# BMS_V3.net
KiCad netlist of a schematic drawn in Altium Designer
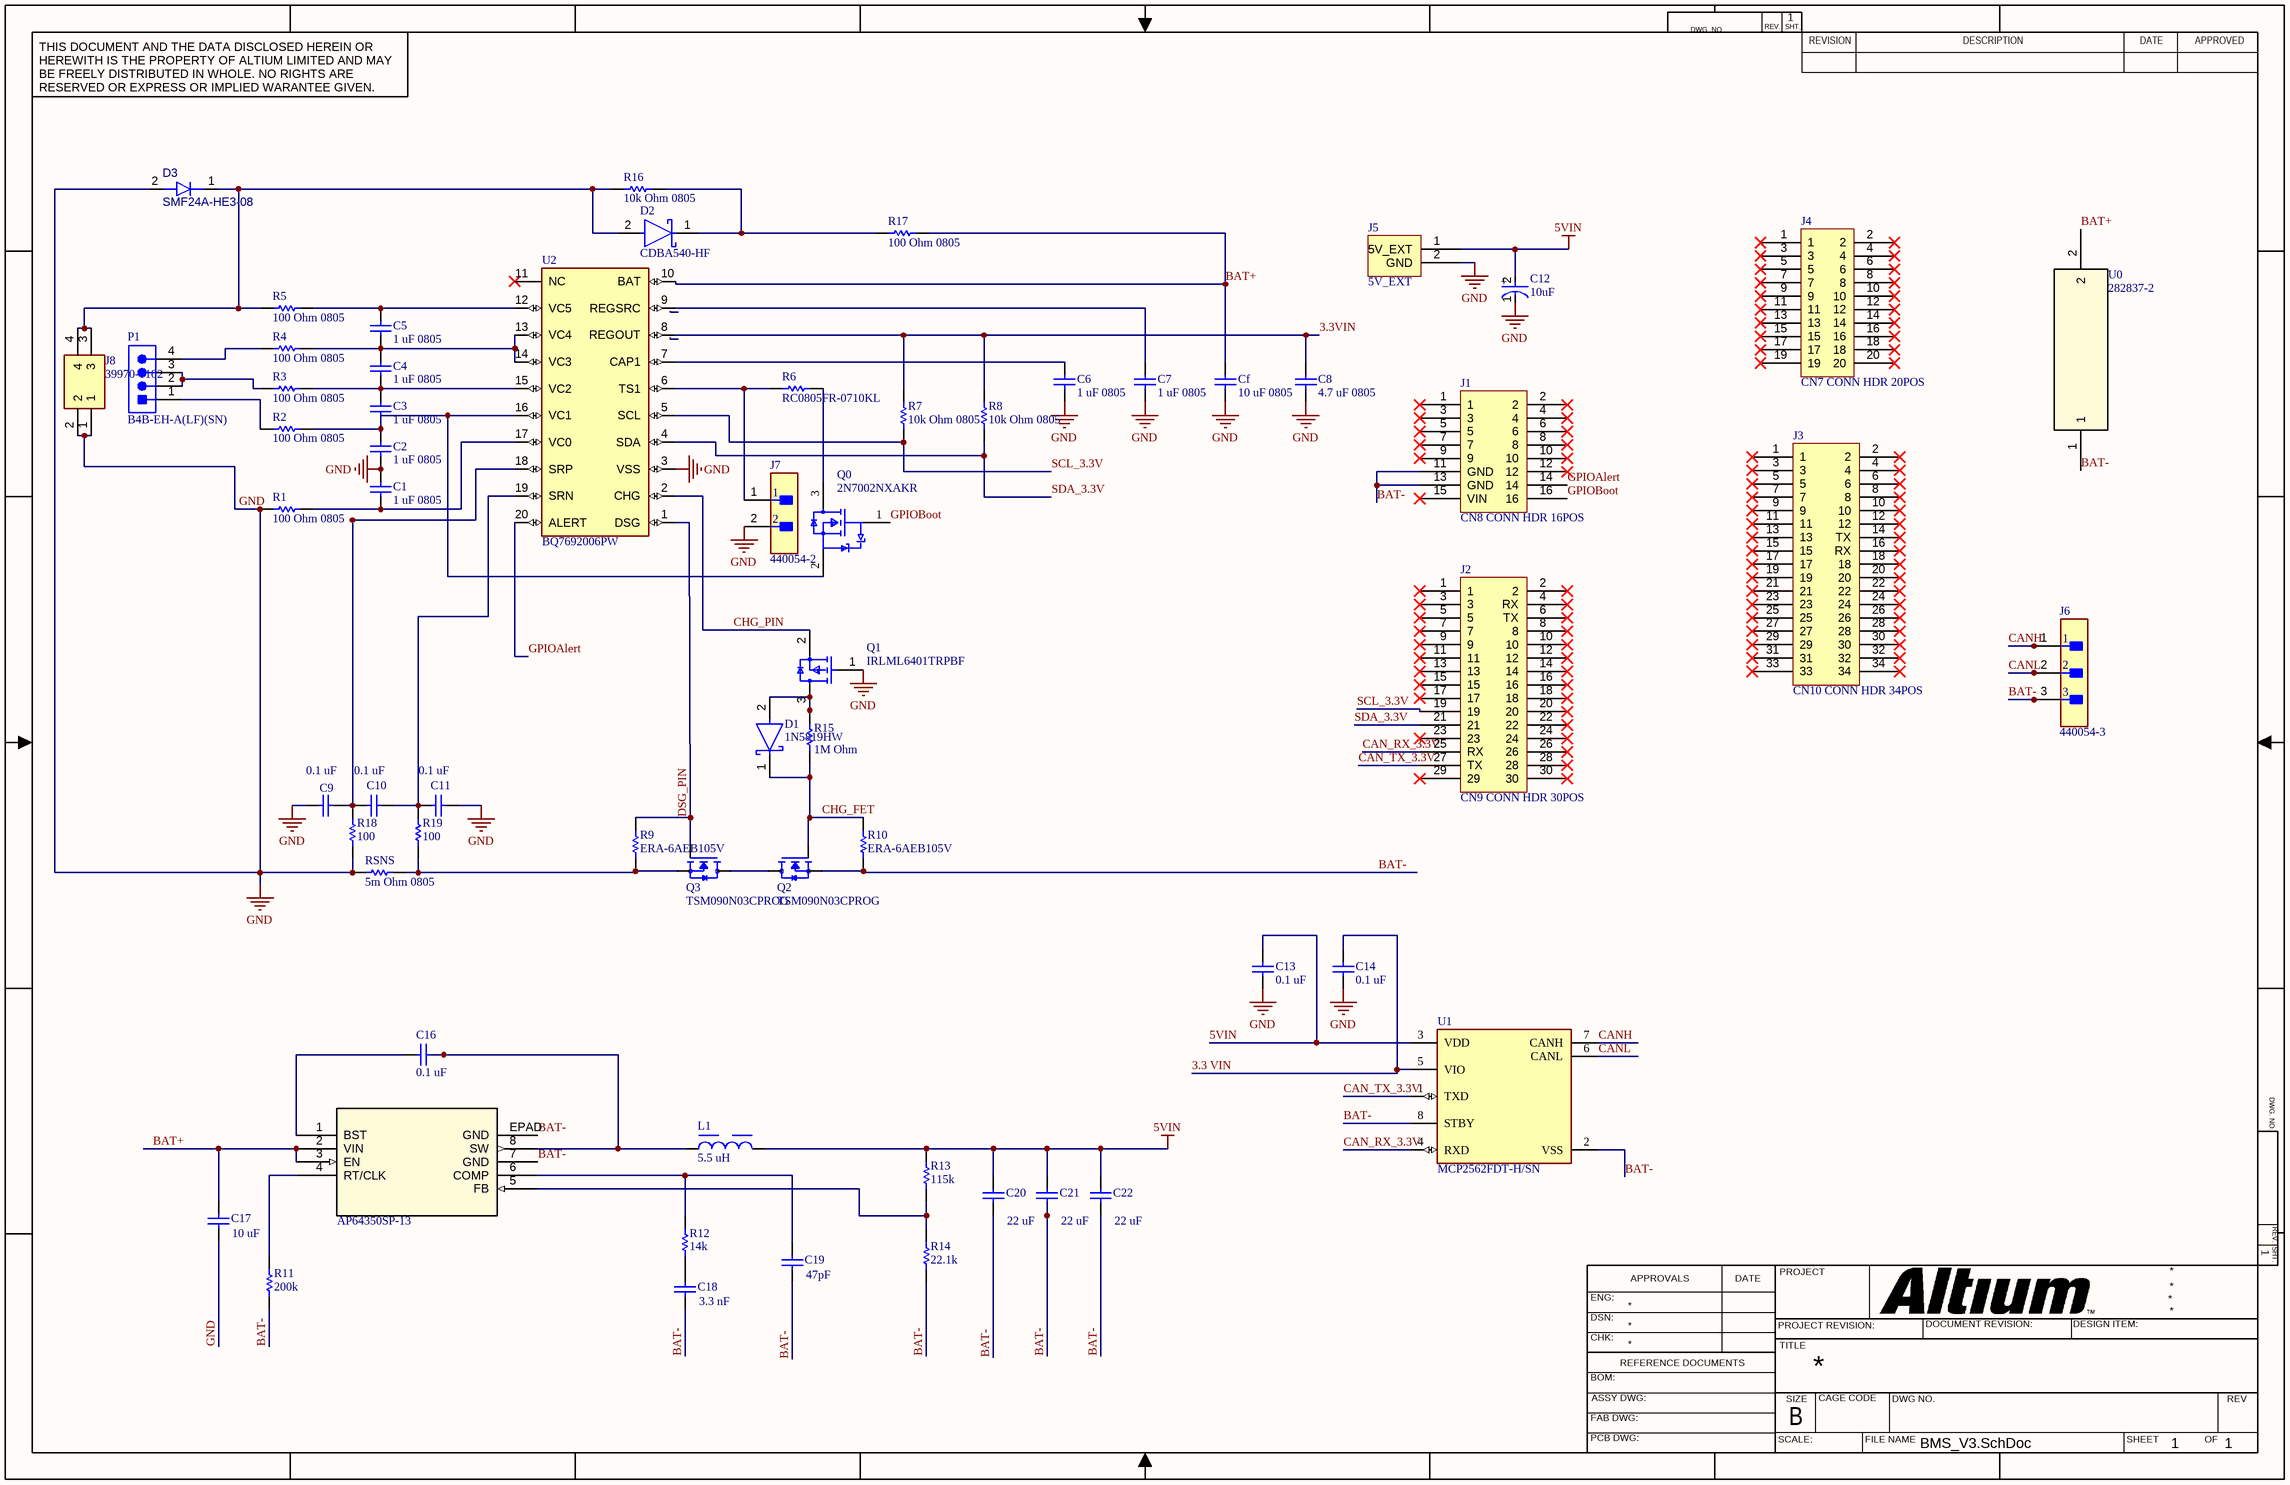
[diagram p0: BMS_V3.SchDoc]

(export (version "E")
  (design (tool "Eeschema 10.0.6"))
  (components
    (comp (ref "C1")
      (value "1 uF 0805")
      (footprint "CAPC2013X140X50LL20T25")
      (fields (field (name "PART NUMBER") "C0805C105K3RACTU") (field (name "MANUFACTURER") "Kemet"))
      (libsource (lib "Altium Content Vault") (part "CAP"))
    )
    (comp (ref "C2")
      (value "1 uF 0805")
      (footprint "CAPC2013X140X50LL20T25")
      (fields (field (name "PART NUMBER") "C0805C105K3RACTU") (field (name "MANUFACTURER") "Kemet"))
      (libsource (lib "Altium Content Vault") (part "CAP"))
    )
    (comp (ref "C3")
      (value "1 uF 0805")
      (footprint "CAPC2013X140X50LL20T25")
      (fields (field (name "PART NUMBER") "C0805C105K3RACTU") (field (name "MANUFACTURER") "Kemet"))
      (libsource (lib "Altium Content Vault") (part "CAP"))
    )
    (comp (ref "C4")
      (value "1 uF 0805")
      (footprint "CAPC2013X140X50LL20T25")
      (fields (field (name "PART NUMBER") "C0805C105K3RACTU") (field (name "MANUFACTURER") "Kemet"))
      (libsource (lib "Altium Content Vault") (part "CAP"))
    )
    (comp (ref "C5")
      (value "1 uF 0805")
      (footprint "CAPC2013X140X50LL20T25")
      (fields (field (name "PART NUMBER") "C0805C105K3RACTU") (field (name "MANUFACTURER") "Kemet"))
      (libsource (lib "Altium Content Vault") (part "CAP"))
    )
    (comp (ref "C6")
      (value "1 uF 0805")
      (footprint "CAPC2013X140X50LL20T25")
      (fields (field (name "PART NUMBER") "C0805C105K3RACTU") (field (name "MANUFACTURER") "Kemet"))
      (libsource (lib "Altium Content Vault") (part "CAP"))
    )
    (comp (ref "C7")
      (value "1 uF 0805")
      (footprint "CAPC2013X140X50LL20T25")
      (fields (field (name "PART NUMBER") "C0805C105K3RACTU") (field (name "MANUFACTURER") "Kemet"))
      (libsource (lib "Altium Content Vault") (part "CAP"))
    )
    (comp (ref "C8")
      (value "4.7 uF 0805")
      (footprint "CAPC2013X140X50LL20T25")
      (fields (field (name "PART NUMBER") "C0805C105K3RACTU") (field (name "MANUFACTURER") "Kemet"))
      (libsource (lib "Altium Content Vault") (part "CAP"))
    )
    (comp (ref "C9")
      (value "0.1 uF")
      (footprint "CAPC2013X140X50LL20T25")
      (fields (field (name "PART NUMBER") "C0805C105K3RACTU") (field (name "MANUFACTURER") "Kemet"))
      (libsource (lib "Altium Content Vault") (part "CAP"))
    )
    (comp (ref "C10")
      (value "0.1 uF")
      (footprint "CAPC2013X140X50LL20T25")
      (fields (field (name "PART NUMBER") "C0805C105K3RACTU") (field (name "MANUFACTURER") "Kemet"))
      (libsource (lib "Altium Content Vault") (part "CAP"))
    )
    (comp (ref "C11")
      (value "0.1 uF")
      (footprint "CAPC2013X140X50LL20T25")
      (fields (field (name "PART NUMBER") "C0805C105K3RACTU") (field (name "MANUFACTURER") "Kemet"))
      (libsource (lib "Altium Content Vault") (part "CAP"))
    )
    (comp (ref "C12")
      (value "10uF")
      (footprint "FP-FKC-MFG")
      (description "CAP ALUM 10UF 20% 50V SMD")
      (fields (field (name "TOLERANCE") "20%") (field (name "VOLTAGE") "50V"))
      (libsource (lib "Altium Content Vault") (part "a00bbbee19879c290e62620ae7e47b1"))
    )
    (comp (ref "C13")
      (value "0.1 uF")
      (footprint "CAPC2013X135X45NL10T25")
      (description "Chip Capacitor, 4.7 uF, +/- 10%, 16 V, -55 to 85 degC, 0805 (2012 Metric), RoHS, Tape and Reel")
      (fields (field (name "TOLERANCE") "10%") (field (name "PARTNUMBER") "GRM21BR61C475KA88L"))
      (libsource (lib "Altium Content Vault") (part "CAP-NP-2"))
    )
    (comp (ref "C14")
      (value "0.1 uF")
      (footprint "CAPC2013X135X45NL10T25")
      (description "Chip Capacitor, 4.7 uF, +/- 10%, 16 V, -55 to 85 degC, 0805 (2012 Metric), RoHS, Tape and Reel")
      (fields (field (name "TOLERANCE") "10%") (field (name "PARTNUMBER") "GRM21BR61C475KA88L"))
      (libsource (lib "Altium Content Vault") (part "CAP-NP-2"))
    )
    (comp (ref "C16")
      (value "0.1 uF")
      (footprint "CAPC2013X135X45NL10T25")
      (description "Chip Capacitor, 4.7 uF, +/- 10%, 16 V, -55 to 85 degC, 0805 (2012 Metric), RoHS, Tape and Reel")
      (fields (field (name "TOLERANCE") "10%") (field (name "PARTNUMBER") "GRM21BR61C475KA88L"))
      (libsource (lib "Altium Content Vault") (part "CAP-NP-2"))
    )
    (comp (ref "C17")
      (value "10 uF")
      (footprint "CAPC2013X135X45NL10T25")
      (description "Chip Capacitor, 4.7 uF, +/- 10%, 16 V, -55 to 85 degC, 0805 (2012 Metric), RoHS, Tape and Reel")
      (fields (field (name "TOLERANCE") "10%") (field (name "PARTNUMBER") "GRM21BR61C475KA88L"))
      (libsource (lib "Altium Content Vault") (part "CAP-NP-2"))
    )
    (comp (ref "C18")
      (value "3.3 nF")
      (footprint "CAPC2013X135X45NL10T25")
      (description "Chip Capacitor, 4.7 uF, +/- 10%, 16 V, -55 to 85 degC, 0805 (2012 Metric), RoHS, Tape and Reel")
      (fields (field (name "TOLERANCE") "10%") (field (name "PARTNUMBER") "GRM21BR61C475KA88L"))
      (libsource (lib "Altium Content Vault") (part "CAP-NP-2"))
    )
    (comp (ref "C19")
      (value "47pF")
      (footprint "CAPC2013X135X45NL10T25")
      (description "Chip Capacitor, 4.7 uF, +/- 10%, 16 V, -55 to 85 degC, 0805 (2012 Metric), RoHS, Tape and Reel")
      (fields (field (name "TOLERANCE") "10%") (field (name "PARTNUMBER") "GRM21BR61C475KA88L"))
      (libsource (lib "Altium Content Vault") (part "CAP-NP-2"))
    )
    (comp (ref "C20")
      (value "22 uF")
      (footprint "CAPC2013X135X45NL10T25")
      (description "Chip Capacitor, 4.7 uF, +/- 10%, 16 V, -55 to 85 degC, 0805 (2012 Metric), RoHS, Tape and Reel")
      (fields (field (name "TOLERANCE") "10%") (field (name "PARTNUMBER") "GRM21BR61C475KA88L"))
      (libsource (lib "Altium Content Vault") (part "CAP-NP-2"))
    )
    (comp (ref "C21")
      (value "22 uF")
      (footprint "CAPC2013X135X45NL10T25")
      (description "Chip Capacitor, 4.7 uF, +/- 10%, 16 V, -55 to 85 degC, 0805 (2012 Metric), RoHS, Tape and Reel")
      (fields (field (name "TOLERANCE") "10%") (field (name "PARTNUMBER") "GRM21BR61C475KA88L"))
      (libsource (lib "Altium Content Vault") (part "CAP-NP-2"))
    )
    (comp (ref "C22")
      (value "22 uF")
      (footprint "CAPC2013X135X45NL10T25")
      (description "Chip Capacitor, 4.7 uF, +/- 10%, 16 V, -55 to 85 degC, 0805 (2012 Metric), RoHS, Tape and Reel")
      (fields (field (name "TOLERANCE") "10%") (field (name "PARTNUMBER") "GRM21BR61C475KA88L"))
      (libsource (lib "Altium Content Vault") (part "CAP-NP-2"))
    )
    (comp (ref "Cf")
      (value "10 uF 0805")
      (footprint "CAPC2013X140X50LL20T25")
      (fields (field (name "PART NUMBER") "C0805C105K3RACTU") (field (name "MANUFACTURER") "Kemet"))
      (libsource (lib "Altium Content Vault") (part "CAP"))
    )
    (comp (ref "D1")
      (value "1N5819HW")
      (footprint "FP-SOD123-IPC_A")
      (description "DIODE SCHOTTKY 40V 1A SOD123")
      (libsource (lib "Altium Content Vault") (part "1d6ec82d83fb6aee721767c19dac4b9"))
    )
    (comp (ref "D2")
      (value "CDBA540-HF")
      (footprint "FP-DO-214AC-MFG")
      (description "DIODE SCHOTTKY 40V 5A DO214AC")
      (fields
        (field (name "OCTOPART") "https://octopart.com/cdba540-hf-comchip-57839773")
        (field (name "MANUFACTURER") "Comchip")
      )
      (libsource (lib "Altium Content Vault") (part "1d6ec82d83fb6aee721767c19dac4b9"))
    )
    (comp (ref "D3")
      (value "SMF24A-HE3-08")
      (footprint "DIOM2818X11N")
      (description "Trans Voltage Suppressor Diode, 1000W, 24V V(RWM), Unidirectional, 1 Element, Silicon, DO-219AB")
      (libsource (lib "Dattu Hariharan") (part "DIODE-2"))
    )
    (comp (ref "J1")
      (value "CN8 CONN HDR 16POS")
      (footprint "CN8_8X2_PADS")
      (description "CN8 CONN HDR 16POS 0.1 STACK")
      (libsource (lib "Dattu Hariharan") (part "CN8 CONN HDR 16POS"))
    )
    (comp (ref "J2")
      (value "CN9 CONN HDR 30POS")
      (footprint "CN9_15X2_PADS")
      (description "CN9 CONN HDR 30 POS  0.1 STACK")
      (libsource (lib "Dattu Hariharan") (part "CN9 CONN HDR 30POS"))
    )
    (comp (ref "J3")
      (value "CN10 CONN HDR 34POS")
      (footprint "CN10_17X2_PADS")
      (description "CN10 CONN HDR 34 POS  0.1 STACK")
      (libsource (lib "Dattu Hariharan") (part "CN10 CONN HDR 34POS"))
    )
    (comp (ref "J4")
      (value "CN7 CONN HDR 20POS")
      (footprint "CN7_10X2_PADS")
      (description "CN7 CONN HDR 20 POS  0.1 STACK")
      (libsource (lib "Dattu Hariharan") (part "CN7 CONN HDR 20POS"))
    )
    (comp (ref "J5")
      (value "5V_EXT")
      (footprint "5V_EXT")
      (libsource (lib "Dattu Hariharan") (part "5V_EXT"))
    )
    (comp (ref "J6")
      (value "440054-3")
      (footprint "FP-440054-3-MFG")
      (description "CONN HEADER VERT 3POS 2MM")
      (fields
        (field (name "OCTOPART") "https://octopart.com/440054-3-te+connectivity-40394845")
        (field (name "MANUFACTURER") "TE Connectivity")
      )
      (libsource (lib "Altium Content Vault") (part "0d3f023dd272f625e17a2be33dea85f"))
    )
    (comp (ref "J7")
      (value "440054-2")
      (footprint "FP-440054-2-MFG")
      (description "CONN HEADER VERT 2POS 2MM")
      (fields
        (field (name "MANUFACTURER") "TE Connectivity")
        (field (name "OCTOPART") "https://octopart.com/440054-2-te+connectivity-40237927")
      )
      (libsource (lib "Altium Content Vault") (part "3bc925449376181038e59eaffc5286c"))
    )
    (comp (ref "J8")
      (value "39970-0102")
      (footprint "399700102:399700102")
      (description "10.16mm Beau Eurostyle Fixed Mount PCB Terminal Block, High Power 40A,  Circuits")
      (fields (field (name "MOUSER PART NUMBER") "538-39970-0102"))
      (libsource (lib "39970-0102") (part "39970-0102"))
    )
    (comp (ref "L1")
      (value "5.5 uH")
      (footprint "WE-HCI_1050")
      (fields (field (name "TOLERANCE") "20%"))
      (libsource (lib "Altium Content Vault") (part "Inductor - 3"))
    )
    (comp (ref "P1")
      (value "B4B-EH-A(LF)(SN)")
      (footprint "JST-B4B-EH-A_V")
      (fields (field (name "MANUFACTURER") "JST"))
      (libsource (lib "Altium Content Vault") (part "CN-1P-M-R4"))
    )
    (comp (ref "Q0")
      (value "2N7002NXAKR")
      (footprint "FP-SOT23-IPC_B")
      (description "2N7002NXAK/SOT23/TO-236AB")
      (libsource (lib "Altium Content Vault") (part "bf18956dcdab3ff4da62eb44f668dfe"))
    )
    (comp (ref "Q1")
      (value "IRLML6401TRPBF")
      (footprint "FP-SOT23-MFG")
      (description "MOSFET P-CH 12V 4.3A SOT-23")
      (fields
        (field (name "MANUFACTURER") "Infineon")
        (field (name "OCTOPART") "https://octopart.com/irlml6401trpbf-infineon-65874987")
      )
      (libsource (lib "Altium Content Vault") (part "28bfa747e7c25bfdd37193474a7f289"))
    )
    (comp (ref "Q2")
      (value "TSM090N03CPROG")
      (footprint "TRANS_TSM090N03CPROG")
      (description "N-Channel 30 V 50A (Tc) 40W (Tc) Surface Mount TO-252 (DPAK)")
      (fields (field (name "MF") "Taiwan Semiconductor"))
      (libsource (lib "Dattu Hariharan") (part "TSM090N03CPROG"))
    )
    (comp (ref "Q3")
      (value "TSM090N03CPROG")
      (footprint "TRANS_TSM090N03CPROG")
      (description "N-Channel 30 V 50A (Tc) 40W (Tc) Surface Mount TO-252 (DPAK)")
      (fields (field (name "MF") "Taiwan Semiconductor"))
      (libsource (lib "Dattu Hariharan") (part "TSM090N03CPROG"))
    )
    (comp (ref "R1")
      (value "100 Ohm 0805")
      (footprint "RESC2013X60X30ML20T20")
      (fields (field (name "PART NUMBER") "RK73H2ATTD1000F") (field (name "MANUFACTURER") "KOA Speer"))
      (libsource (lib "Altium Content Vault") (part "RES"))
    )
    (comp (ref "R2")
      (value "100 Ohm 0805")
      (footprint "RESC2013X60X30ML20T20")
      (fields (field (name "PART NUMBER") "RK73H2ATTD1000F") (field (name "MANUFACTURER") "KOA Speer"))
      (libsource (lib "Altium Content Vault") (part "RES"))
    )
    (comp (ref "R3")
      (value "100 Ohm 0805")
      (footprint "RESC2013X60X30ML20T20")
      (fields (field (name "PART NUMBER") "RK73H2ATTD1000F") (field (name "MANUFACTURER") "KOA Speer"))
      (libsource (lib "Altium Content Vault") (part "RES"))
    )
    (comp (ref "R4")
      (value "100 Ohm 0805")
      (footprint "RESC2013X60X30ML20T20")
      (fields (field (name "PART NUMBER") "RK73H2ATTD1000F") (field (name "MANUFACTURER") "KOA Speer"))
      (libsource (lib "Altium Content Vault") (part "RES"))
    )
    (comp (ref "R5")
      (value "100 Ohm 0805")
      (footprint "RESC2013X60X30ML20T20")
      (fields (field (name "PART NUMBER") "RK73H2ATTD1000F") (field (name "MANUFACTURER") "KOA Speer"))
      (libsource (lib "Altium Content Vault") (part "RES"))
    )
    (comp (ref "R6")
      (value "RC0805FR-0710KL")
      (footprint "RESC2013X60X35NL10T20")
      (description "Chip Resistor, 10 KOhm, +/- 1%, 0.125 W, -55 to 155 degC, 0805 (2012 Metric), RoHS, Tape and Reel")
      (fields (field (name "MANUFACTURER") "Yageo"))
      (libsource (lib "Altium Content Vault") (part "RES-2"))
    )
    (comp (ref "R7")
      (value "10k Ohm 0805")
      (footprint "RESC2013X60X30ML20T20")
      (fields (field (name "PART NUMBER") "RK73H2ATTD1000F") (field (name "MANUFACTURER") "KOA Speer"))
      (libsource (lib "Altium Content Vault") (part "RES"))
    )
    (comp (ref "R8")
      (value "10k Ohm 0805")
      (footprint "RESC2013X60X30ML20T20")
      (fields (field (name "PART NUMBER") "RK73H2ATTD1000F") (field (name "MANUFACTURER") "KOA Speer"))
      (libsource (lib "Altium Content Vault") (part "RES"))
    )
    (comp (ref "R9")
      (value "ERA-6AEB105V")
      (footprint "RESC2013X60X40LL20T25")
      (fields (field (name "MANUFACTURER") "Panasonic"))
      (libsource (lib "Altium Content Vault") (part "RES"))
    )
    (comp (ref "R10")
      (value "ERA-6AEB105V")
      (footprint "RESC2013X60X40LL20T25")
      (fields (field (name "MANUFACTURER") "Panasonic"))
      (libsource (lib "Altium Content Vault") (part "RES"))
    )
    (comp (ref "R11")
      (value "200k")
      (footprint "RESC2013X60X35ML10T20")
      (description "Chip Resistor, 1 KOhm, +/- 1%, 125 mW, -55 to 155 degC, 0805 (2012 Metric), RoHS, Tape and Reel")
      (fields (field (name "TOLERANCE") "1%") (field (name "MANUFACTURER") "Yageo"))
      (libsource (lib "Altium Content Vault") (part "RES-2"))
    )
    (comp (ref "R12")
      (value "14k")
      (footprint "RESC2013X60X35ML10T20")
      (description "Chip Resistor, 1 KOhm, +/- 1%, 125 mW, -55 to 155 degC, 0805 (2012 Metric), RoHS, Tape and Reel")
      (fields (field (name "TOLERANCE") "1%") (field (name "MANUFACTURER") "Yageo"))
      (libsource (lib "Altium Content Vault") (part "RES-2"))
    )
    (comp (ref "R13")
      (value "115k")
      (footprint "RESC2013X60X35ML10T20")
      (description "Chip Resistor, 1 KOhm, +/- 1%, 125 mW, -55 to 155 degC, 0805 (2012 Metric), RoHS, Tape and Reel")
      (fields (field (name "TOLERANCE") "1%") (field (name "MANUFACTURER") "Yageo"))
      (libsource (lib "Altium Content Vault") (part "RES-2"))
    )
    (comp (ref "R14")
      (value "22.1k")
      (footprint "RESC2013X60X35ML10T20")
      (description "Chip Resistor, 1 KOhm, +/- 1%, 125 mW, -55 to 155 degC, 0805 (2012 Metric), RoHS, Tape and Reel")
      (fields (field (name "TOLERANCE") "1%") (field (name "MANUFACTURER") "Yageo"))
      (libsource (lib "Altium Content Vault") (part "RES-2"))
    )
    (comp (ref "R15")
      (value "1M Ohm")
      (footprint "RESC2013X60X40LL20T25")
      (fields (field (name "PART NUMBER") "ERA-6AEB105V") (field (name "MANUFACTURER") "Panasonic"))
      (libsource (lib "Altium Content Vault") (part "RES"))
    )
    (comp (ref "R16")
      (value "10k Ohm 0805")
      (footprint "RESC2013X60X30ML20T20")
      (fields (field (name "PART NUMBER") "RK73H2ATTD1000F") (field (name "MANUFACTURER") "KOA Speer"))
      (libsource (lib "Altium Content Vault") (part "RES"))
    )
    (comp (ref "R17")
      (value "100 Ohm 0805")
      (footprint "RESC2013X60X30ML20T20")
      (fields (field (name "PART NUMBER") "RK73H2ATTD1000F") (field (name "MANUFACTURER") "KOA Speer"))
      (libsource (lib "Altium Content Vault") (part "RES"))
    )
    (comp (ref "R18")
      (value "100")
      (footprint "RESC2013X50X30LL20T20")
      (fields (field (name "MANUFACTURER") "Vishay Dale") (field (name "PART NUMBER") "CRCW0805100RFKEA"))
      (libsource (lib "Altium Content Vault") (part "RES"))
    )
    (comp (ref "R19")
      (value "100")
      (footprint "RESC2013X50X30LL20T20")
      (fields (field (name "MANUFACTURER") "Vishay Dale") (field (name "PART NUMBER") "CRCW0805100RFKEA"))
      (libsource (lib "Altium Content Vault") (part "RES"))
    )
    (comp (ref "RSNS")
      (value "5m Ohm 0805")
      (footprint "RESC2013X60X30ML20T20")
      (fields (field (name "PART NUMBER") "RK73H2ATTD1000F") (field (name "MANUFACTURER") "KOA Speer"))
      (libsource (lib "Altium Content Vault") (part "RES"))
    )
    (comp (ref "U0")
      (value "282837-2")
      (footprint "282837-2_TYC")
      (description "No Description Available")
      (libsource (lib "Dattu Hariharan") (part "282837-2"))
    )
    (comp (ref "U1")
      (value "MCP2562FDT-H/SN")
      (footprint "FP-C04-057-SN-IPC_A")
      (description "IC TRANSCEIVER 1/1 8SOIC")
      (libsource (lib "Altium Content Vault") (part "d4eccbb03d796c5d2cef85367bb866b"))
    )
    (comp (ref "U2")
      (value "BQ7692006PW")
      (footprint "BQ7692006PW")
      (description "3 to 5-Series Cell Li-Ion and Li-Phosphate Battery Monitor (bq76940 Family)")
      (fields (field (name "MF") "Texas Instruments"))
      (libsource (lib "Dattu Hariharan") (part "BQ7692006PW"))
    )
    (comp (ref "U3")
      (value "AP64350SP-13")
      (footprint "SO-8EP_DIO")
      (description "No Description Available")
      (libsource (lib "Dattu Hariharan") (part "AP64350SP-13"))
    )
  )
  (nets
    (net (code "1") (name "/3.3 VIN") (class "Default")
      (node (ref "C14") (pin "2") (pinfunction "2_2") (pintype "passive"))
      (node (ref "U1") (pin "5") (pinfunction "VIO_5") (pintype "power_in"))
    )
    (net (code "2") (name "/3.3VIN") (class "Default")
      (node (ref "C8") (pin "2") (pinfunction "2_2") (pintype "passive"))
      (node (ref "R7") (pin "2") (pinfunction "2_2") (pintype "passive"))
      (node (ref "R8") (pin "2") (pinfunction "2_2") (pintype "passive"))
      (node (ref "U2") (pin "8") (pinfunction "REGOUT_8") (pintype "bidirectional"))
    )
    (net (code "4") (name "/BAT+") (class "Default")
      (node (ref "C17") (pin "2") (pinfunction "2_2") (pintype "passive"))
      (node (ref "Cf") (pin "2") (pinfunction "2_2") (pintype "passive"))
      (node (ref "R17") (pin "2") (pinfunction "2_2") (pintype "passive"))
      (node (ref "U0") (pin "2") (pinfunction "2_2") (pintype "passive"))
      (node (ref "U2") (pin "10") (pinfunction "BAT_10") (pintype "bidirectional"))
      (node (ref "U3") (pin "2") (pinfunction "VIN_2") (pintype "power_in"))
      (node (ref "U3") (pin "3") (pinfunction "EN_3") (pintype "input"))
    )
    (net (code "5") (name "/BAT-") (class "Default")
      (node (ref "C18") (pin "1") (pinfunction "1_1") (pintype "passive"))
      (node (ref "C19") (pin "1") (pinfunction "1_1") (pintype "passive"))
      (node (ref "C20") (pin "1") (pinfunction "1_1") (pintype "passive"))
      (node (ref "C21") (pin "1") (pinfunction "1_1") (pintype "passive"))
      (node (ref "C22") (pin "1") (pinfunction "1_1") (pintype "passive"))
      (node (ref "J1") (pin "11") (pinfunction "GND_11") (pintype "passive"))
      (node (ref "J1") (pin "13") (pinfunction "GND_13") (pintype "passive"))
      (node (ref "J6") (pin "3") (pinfunction "3_3") (pintype "passive"))
      (node (ref "Q2") (pin "3") (pinfunction "S_3") (pintype "passive"))
      (node (ref "R10") (pin "1") (pinfunction "1_1") (pintype "passive"))
      (node (ref "R11") (pin "1") (pinfunction "1_1") (pintype "passive"))
      (node (ref "R14") (pin "1") (pinfunction "1_1") (pintype "passive"))
      (node (ref "U0") (pin "1") (pinfunction "1_1") (pintype "passive"))
      (node (ref "U1") (pin "2") (pinfunction "VSS_2") (pintype "power_in"))
      (node (ref "U1") (pin "8") (pinfunction "STBY_8") (pintype "passive"))
      (node (ref "U3") (pin "7") (pinfunction "GND_7") (pintype "power_in"))
      (node (ref "U3") (pin "EPAD") (pinfunction "GND_EPAD") (pintype "power_in"))
    )
    (net (code "6") (name "/CANH") (class "Default")
      (node (ref "J6") (pin "1") (pinfunction "1_1") (pintype "passive"))
      (node (ref "U1") (pin "7") (pinfunction "CANH_7") (pintype "passive"))
    )
    (net (code "7") (name "/CANL") (class "Default")
      (node (ref "J6") (pin "2") (pinfunction "2_2") (pintype "passive"))
      (node (ref "U1") (pin "6") (pinfunction "CANL_6") (pintype "passive"))
    )
    (net (code "8") (name "/CAN_RX_3.3V") (class "Default")
      (node (ref "J2") (pin "25") (pinfunction "RX_25") (pintype "passive"))
      (node (ref "U1") (pin "4") (pinfunction "RXD_4") (pintype "bidirectional"))
    )
    (net (code "9") (name "/CAN_TX_3.3V") (class "Default")
      (node (ref "J2") (pin "27") (pinfunction "TX_27") (pintype "passive"))
      (node (ref "U1") (pin "1") (pinfunction "TXD_1") (pintype "bidirectional"))
    )
    (net (code "10") (name "/CHG_FET") (class "Default")
      (node (ref "D1") (pin "1") (pinfunction "C_1") (pintype "passive"))
      (node (ref "Q2") (pin "1") (pinfunction "G_1") (pintype "passive"))
      (node (ref "R10") (pin "2") (pinfunction "2_2") (pintype "passive"))
      (node (ref "R15") (pin "1") (pinfunction "1_1") (pintype "passive"))
    )
    (net (code "11") (name "/CHG_PIN") (class "Default")
      (node (ref "Q1") (pin "2") (pinfunction "S_2") (pintype "passive"))
      (node (ref "U2") (pin "2") (pinfunction "CHG_2") (pintype "bidirectional"))
    )
    (net (code "12") (name "/DSG_PIN") (class "Default")
      (node (ref "Q3") (pin "1") (pinfunction "G_1") (pintype "passive"))
      (node (ref "R9") (pin "2") (pinfunction "2_2") (pintype "passive"))
      (node (ref "U2") (pin "1") (pinfunction "DSG_1") (pintype "bidirectional"))
    )
    (net (code "13") (name "/GPIOAlert") (class "Default")
      (node (ref "J1") (pin "14") (pinfunction "14_14") (pintype "passive"))
      (node (ref "U2") (pin "20") (pinfunction "ALERT_20") (pintype "bidirectional"))
    )
    (net (code "14") (name "/GPIOBoot") (class "Default")
      (node (ref "J1") (pin "16") (pinfunction "16_16") (pintype "passive"))
      (node (ref "Q0") (pin "1") (pinfunction "G_1") (pintype "passive"))
    )
    (net (code "15") (name "/SCL_3.3V") (class "Default")
      (node (ref "J2") (pin "19") (pinfunction "19_19") (pintype "passive"))
      (node (ref "R7") (pin "1") (pinfunction "1_1") (pintype "passive"))
      (node (ref "U2") (pin "5") (pinfunction "SCL_5") (pintype "bidirectional"))
    )
    (net (code "16") (name "/SDA_3.3V") (class "Default")
      (node (ref "J2") (pin "21") (pinfunction "21_21") (pintype "passive"))
      (node (ref "R8") (pin "1") (pinfunction "1_1") (pintype "passive"))
      (node (ref "U2") (pin "4") (pinfunction "SDA_4") (pintype "bidirectional"))
    )
    (net (code "17") (name "5VIN") (class "Default")
      (node (ref "C12") (pin "2") (pinfunction "A_2") (pintype "passive"))
      (node (ref "C13") (pin "2") (pinfunction "2_2") (pintype "passive"))
      (node (ref "C20") (pin "2") (pinfunction "2_2") (pintype "passive"))
      (node (ref "C21") (pin "2") (pinfunction "2_2") (pintype "passive"))
      (node (ref "C22") (pin "2") (pinfunction "2_2") (pintype "passive"))
      (node (ref "J5") (pin "1") (pinfunction "5V_EXT_1") (pintype "passive"))
      (node (ref "L1") (pin "2") (pinfunction "2_2") (pintype "passive"))
      (node (ref "R13") (pin "2") (pinfunction "2_2") (pintype "passive"))
      (node (ref "U1") (pin "3") (pinfunction "VDD_3") (pintype "power_in"))
    )
    (net (code "18") (name "GND") (class "Default")
      (node (ref "C1") (pin "2") (pinfunction "2_2") (pintype "passive"))
      (node (ref "C11") (pin "1") (pinfunction "1_1") (pintype "passive"))
      (node (ref "C12") (pin "1") (pinfunction "C_1") (pintype "passive"))
      (node (ref "C13") (pin "1") (pinfunction "1_1") (pintype "passive"))
      (node (ref "C14") (pin "1") (pinfunction "1_1") (pintype "passive"))
      (node (ref "C17") (pin "1") (pinfunction "1_1") (pintype "passive"))
      (node (ref "C2") (pin "1") (pinfunction "1_1") (pintype "passive"))
      (node (ref "C6") (pin "1") (pinfunction "1_1") (pintype "passive"))
      (node (ref "C7") (pin "1") (pinfunction "1_1") (pintype "passive"))
      (node (ref "C8") (pin "1") (pinfunction "1_1") (pintype "passive"))
      (node (ref "C9") (pin "2") (pinfunction "2_2") (pintype "passive"))
      (node (ref "Cf") (pin "1") (pinfunction "1_1") (pintype "passive"))
      (node (ref "D3") (pin "2") (pinfunction "A_2") (pintype "passive"))
      (node (ref "J5") (pin "2") (pinfunction "GND_2") (pintype "passive"))
      (node (ref "J7") (pin "2") (pinfunction "2_2") (pintype "passive"))
      (node (ref "J8") (pin "1") (pinfunction "1_1") (pintype "passive"))
      (node (ref "J8") (pin "2") (pinfunction "2_2") (pintype "passive"))
      (node (ref "Q1") (pin "1") (pinfunction "G_1") (pintype "passive"))
      (node (ref "R1") (pin "1") (pinfunction "1_1") (pintype "passive"))
      (node (ref "R18") (pin "1") (pinfunction "1_1") (pintype "passive"))
      (node (ref "RSNS") (pin "2") (pinfunction "2_2") (pintype "passive"))
      (node (ref "U2") (pin "3") (pinfunction "VSS_3") (pintype "bidirectional"))
    )
    (net (code "19") (name "Net-(C18-Pad2)") (class "Default")
      (node (ref "C18") (pin "2") (pinfunction "2_2") (pintype "passive"))
      (node (ref "R12") (pin "1") (pinfunction "1_1") (pintype "passive"))
    )
    (net (code "20") (name "Net-(D1-A)") (class "Default")
      (node (ref "D1") (pin "2") (pinfunction "A_2") (pintype "passive"))
      (node (ref "Q1") (pin "3") (pinfunction "D_3") (pintype "passive"))
      (node (ref "R15") (pin "2") (pinfunction "2_2") (pintype "passive"))
    )
    (net (code "21") (name "Net-(D2-A)") (class "Default")
      (node (ref "D2") (pin "2") (pinfunction "A_2") (pintype "passive"))
      (node (ref "D3") (pin "1") (pinfunction "K_1") (pintype "passive"))
      (node (ref "J8") (pin "3") (pinfunction "3_3") (pintype "passive"))
      (node (ref "J8") (pin "4") (pinfunction "4_4") (pintype "passive"))
      (node (ref "R16") (pin "1") (pinfunction "1_1") (pintype "passive"))
      (node (ref "R5") (pin "1") (pinfunction "1_1") (pintype "passive"))
    )
    (net (code "22") (name "Net-(D2-C)") (class "Default")
      (node (ref "D2") (pin "1") (pinfunction "C_1") (pintype "passive"))
      (node (ref "R16") (pin "2") (pinfunction "2_2") (pintype "passive"))
      (node (ref "R17") (pin "1") (pinfunction "1_1") (pintype "passive"))
    )
    (net (code "23") (name "Net-(P1-Pad1)") (class "Default")
      (node (ref "P1") (pin "1") (pinfunction "1_1") (pintype "passive"))
      (node (ref "R2") (pin "1") (pinfunction "1_1") (pintype "passive"))
    )
    (net (code "24") (name "Net-(P1-Pad2)") (class "Default")
      (node (ref "P1") (pin "2") (pinfunction "2_2") (pintype "passive"))
      (node (ref "P1") (pin "3") (pinfunction "3_3") (pintype "passive"))
      (node (ref "R3") (pin "1") (pinfunction "1_1") (pintype "passive"))
    )
    (net (code "25") (name "Net-(P1-Pad4)") (class "Default")
      (node (ref "P1") (pin "4") (pinfunction "4_4") (pintype "passive"))
      (node (ref "R4") (pin "1") (pinfunction "1_1") (pintype "passive"))
    )
    (net (code "26") (name "Net-(Q0-D)") (class "Default")
      (node (ref "Q0") (pin "3") (pinfunction "D_3") (pintype "passive"))
      (node (ref "R6") (pin "2") (pinfunction "2_2") (pintype "passive"))
    )
    (net (code "27") (name "Net-(Q0-S)") (class "Default")
      (node (ref "C2") (pin "2") (pinfunction "2_2") (pintype "passive"))
      (node (ref "C3") (pin "1") (pinfunction "1_1") (pintype "passive"))
      (node (ref "Q0") (pin "2") (pinfunction "S_2") (pintype "passive"))
      (node (ref "R2") (pin "2") (pinfunction "2_2") (pintype "passive"))
      (node (ref "U2") (pin "16") (pinfunction "VC1_16") (pintype "bidirectional"))
    )
    (net (code "28") (name "Net-(Q2-D)") (class "Default")
      (node (ref "Q2") (pin "2") (pinfunction "D_2") (pintype "passive"))
      (node (ref "Q3") (pin "2") (pinfunction "D_2") (pintype "passive"))
    )
    (net (code "29") (name "Net-(Q3-S)") (class "Default")
      (node (ref "Q3") (pin "3") (pinfunction "S_3") (pintype "passive"))
      (node (ref "R19") (pin "1") (pinfunction "1_1") (pintype "passive"))
      (node (ref "R9") (pin "1") (pinfunction "1_1") (pintype "passive"))
      (node (ref "RSNS") (pin "1") (pinfunction "1_1") (pintype "passive"))
    )
    (net (code "30") (name "Net-(U2-CAP1)") (class "Default")
      (node (ref "C6") (pin "2") (pinfunction "2_2") (pintype "passive"))
      (node (ref "U2") (pin "7") (pinfunction "CAP1_7") (pintype "bidirectional"))
    )
    (net (code "31") (name "Net-(U2-REGSRC)") (class "Default")
      (node (ref "C7") (pin "2") (pinfunction "2_2") (pintype "passive"))
      (node (ref "U2") (pin "9") (pinfunction "REGSRC_9") (pintype "bidirectional"))
    )
    (net (code "32") (name "Net-(U2-SRN)") (class "Default")
      (node (ref "C10") (pin "1") (pinfunction "1_1") (pintype "passive"))
      (node (ref "C11") (pin "2") (pinfunction "2_2") (pintype "passive"))
      (node (ref "R19") (pin "2") (pinfunction "2_2") (pintype "passive"))
      (node (ref "U2") (pin "19") (pinfunction "SRN_19") (pintype "bidirectional"))
    )
    (net (code "33") (name "Net-(U2-SRP)") (class "Default")
      (node (ref "C10") (pin "2") (pinfunction "2_2") (pintype "passive"))
      (node (ref "C9") (pin "1") (pinfunction "1_1") (pintype "passive"))
      (node (ref "R18") (pin "2") (pinfunction "2_2") (pintype "passive"))
      (node (ref "U2") (pin "18") (pinfunction "SRP_18") (pintype "bidirectional"))
    )
    (net (code "34") (name "Net-(U2-TS1)") (class "Default")
      (node (ref "J7") (pin "1") (pinfunction "1_1") (pintype "passive"))
      (node (ref "R6") (pin "1") (pinfunction "1_1") (pintype "passive"))
      (node (ref "U2") (pin "6") (pinfunction "TS1_6") (pintype "bidirectional"))
    )
    (net (code "35") (name "Net-(U2-VC0)") (class "Default")
      (node (ref "C1") (pin "1") (pinfunction "1_1") (pintype "passive"))
      (node (ref "R1") (pin "2") (pinfunction "2_2") (pintype "passive"))
      (node (ref "U2") (pin "17") (pinfunction "VC0_17") (pintype "bidirectional"))
    )
    (net (code "36") (name "Net-(U2-VC2)") (class "Default")
      (node (ref "C3") (pin "2") (pinfunction "2_2") (pintype "passive"))
      (node (ref "C4") (pin "1") (pinfunction "1_1") (pintype "passive"))
      (node (ref "R3") (pin "2") (pinfunction "2_2") (pintype "passive"))
      (node (ref "U2") (pin "15") (pinfunction "VC2_15") (pintype "bidirectional"))
    )
    (net (code "37") (name "Net-(U2-VC3)") (class "Default")
      (node (ref "C4") (pin "2") (pinfunction "2_2") (pintype "passive"))
      (node (ref "C5") (pin "1") (pinfunction "1_1") (pintype "passive"))
      (node (ref "R4") (pin "2") (pinfunction "2_2") (pintype "passive"))
      (node (ref "U2") (pin "13") (pinfunction "VC4_13") (pintype "bidirectional"))
      (node (ref "U2") (pin "14") (pinfunction "VC3_14") (pintype "bidirectional"))
    )
    (net (code "38") (name "Net-(U2-VC5)") (class "Default")
      (node (ref "C5") (pin "2") (pinfunction "2_2") (pintype "passive"))
      (node (ref "R5") (pin "2") (pinfunction "2_2") (pintype "passive"))
      (node (ref "U2") (pin "12") (pinfunction "VC5_12") (pintype "bidirectional"))
    )
    (net (code "39") (name "Net-(U3-BST)") (class "Default")
      (node (ref "C16") (pin "2") (pinfunction "2_2") (pintype "passive"))
      (node (ref "U3") (pin "1") (pinfunction "BST_1") (pintype "power_in"))
    )
    (net (code "40") (name "Net-(U3-COMP)") (class "Default")
      (node (ref "C19") (pin "2") (pinfunction "2_2") (pintype "passive"))
      (node (ref "R12") (pin "2") (pinfunction "2_2") (pintype "passive"))
      (node (ref "U3") (pin "6") (pinfunction "COMP_6") (pintype "passive"))
    )
    (net (code "41") (name "Net-(U3-FB)") (class "Default")
      (node (ref "R13") (pin "1") (pinfunction "1_1") (pintype "passive"))
      (node (ref "R14") (pin "2") (pinfunction "2_2") (pintype "passive"))
      (node (ref "U3") (pin "5") (pinfunction "FB_5") (pintype "input"))
    )
    (net (code "42") (name "Net-(U3-RT{slash}CLK)") (class "Default")
      (node (ref "R11") (pin "2") (pinfunction "2_2") (pintype "passive"))
      (node (ref "U3") (pin "4") (pinfunction "RT/CLK_4") (pintype "passive"))
    )
    (net (code "43") (name "Net-(U3-SW)") (class "Default")
      (node (ref "C16") (pin "1") (pinfunction "1_1") (pintype "passive"))
      (node (ref "L1") (pin "1") (pinfunction "1_1") (pintype "passive"))
      (node (ref "U3") (pin "8") (pinfunction "SW_8") (pintype "output"))
    )
    (net (code "44") (name "unconnected-(J1-Pad1)") (class "Default")
      (node (ref "J1") (pin "1") (pinfunction "1_1") (pintype "passive+no_connect"))
    )
    (net (code "45") (name "unconnected-(J1-Pad2)") (class "Default")
      (node (ref "J1") (pin "2") (pinfunction "2_2") (pintype "passive+no_connect"))
    )
    (net (code "46") (name "unconnected-(J1-Pad3)") (class "Default")
      (node (ref "J1") (pin "3") (pinfunction "3_3") (pintype "passive+no_connect"))
    )
    (net (code "47") (name "unconnected-(J1-Pad4)") (class "Default")
      (node (ref "J1") (pin "4") (pinfunction "4_4") (pintype "passive+no_connect"))
    )
    (net (code "48") (name "unconnected-(J1-Pad5)") (class "Default")
      (node (ref "J1") (pin "5") (pinfunction "5_5") (pintype "passive+no_connect"))
    )
    (net (code "49") (name "unconnected-(J1-Pad6)") (class "Default")
      (node (ref "J1") (pin "6") (pinfunction "6_6") (pintype "passive+no_connect"))
    )
    (net (code "50") (name "unconnected-(J1-Pad7)") (class "Default")
      (node (ref "J1") (pin "7") (pinfunction "7_7") (pintype "passive+no_connect"))
    )
    (net (code "51") (name "unconnected-(J1-Pad8)") (class "Default")
      (node (ref "J1") (pin "8") (pinfunction "8_8") (pintype "passive+no_connect"))
    )
    (net (code "52") (name "unconnected-(J1-Pad9)") (class "Default")
      (node (ref "J1") (pin "9") (pinfunction "9_9") (pintype "passive+no_connect"))
    )
    (net (code "53") (name "unconnected-(J1-Pad10)") (class "Default")
      (node (ref "J1") (pin "10") (pinfunction "10_10") (pintype "passive+no_connect"))
    )
    (net (code "54") (name "unconnected-(J1-Pad12)") (class "Default")
      (node (ref "J1") (pin "12") (pinfunction "12_12") (pintype "passive+no_connect"))
    )
    (net (code "55") (name "unconnected-(J1-VIN-Pad15)") (class "Default")
      (node (ref "J1") (pin "15") (pinfunction "VIN_15") (pintype "passive+no_connect"))
    )
    (net (code "56") (name "unconnected-(J2-Pad1)") (class "Default")
      (node (ref "J2") (pin "1") (pinfunction "1_1") (pintype "passive+no_connect"))
    )
    (net (code "57") (name "unconnected-(J2-Pad2)") (class "Default")
      (node (ref "J2") (pin "2") (pinfunction "2_2") (pintype "passive+no_connect"))
    )
    (net (code "58") (name "unconnected-(J2-Pad3)") (class "Default")
      (node (ref "J2") (pin "3") (pinfunction "3_3") (pintype "passive+no_connect"))
    )
    (net (code "59") (name "unconnected-(J2-Pad5)") (class "Default")
      (node (ref "J2") (pin "5") (pinfunction "5_5") (pintype "passive+no_connect"))
    )
    (net (code "60") (name "unconnected-(J2-Pad7)") (class "Default")
      (node (ref "J2") (pin "7") (pinfunction "7_7") (pintype "passive+no_connect"))
    )
    (net (code "61") (name "unconnected-(J2-Pad8)") (class "Default")
      (node (ref "J2") (pin "8") (pinfunction "8_8") (pintype "passive+no_connect"))
    )
    (net (code "62") (name "unconnected-(J2-Pad9)") (class "Default")
      (node (ref "J2") (pin "9") (pinfunction "9_9") (pintype "passive+no_connect"))
    )
    (net (code "63") (name "unconnected-(J2-Pad10)") (class "Default")
      (node (ref "J2") (pin "10") (pinfunction "10_10") (pintype "passive+no_connect"))
    )
    (net (code "64") (name "unconnected-(J2-Pad11)") (class "Default")
      (node (ref "J2") (pin "11") (pinfunction "11_11") (pintype "passive+no_connect"))
    )
    (net (code "65") (name "unconnected-(J2-Pad12)") (class "Default")
      (node (ref "J2") (pin "12") (pinfunction "12_12") (pintype "passive+no_connect"))
    )
    (net (code "66") (name "unconnected-(J2-Pad13)") (class "Default")
      (node (ref "J2") (pin "13") (pinfunction "13_13") (pintype "passive+no_connect"))
    )
    (net (code "67") (name "unconnected-(J2-Pad14)") (class "Default")
      (node (ref "J2") (pin "14") (pinfunction "14_14") (pintype "passive+no_connect"))
    )
    (net (code "68") (name "unconnected-(J2-Pad15)") (class "Default")
      (node (ref "J2") (pin "15") (pinfunction "15_15") (pintype "passive+no_connect"))
    )
    (net (code "69") (name "unconnected-(J2-Pad16)") (class "Default")
      (node (ref "J2") (pin "16") (pinfunction "16_16") (pintype "passive+no_connect"))
    )
    (net (code "70") (name "unconnected-(J2-Pad17)") (class "Default")
      (node (ref "J2") (pin "17") (pinfunction "17_17") (pintype "passive+no_connect"))
    )
    (net (code "71") (name "unconnected-(J2-Pad18)") (class "Default")
      (node (ref "J2") (pin "18") (pinfunction "18_18") (pintype "passive+no_connect"))
    )
    (net (code "72") (name "unconnected-(J2-Pad20)") (class "Default")
      (node (ref "J2") (pin "20") (pinfunction "20_20") (pintype "passive+no_connect"))
    )
    (net (code "73") (name "unconnected-(J2-Pad22)") (class "Default")
      (node (ref "J2") (pin "22") (pinfunction "22_22") (pintype "passive+no_connect"))
    )
    (net (code "74") (name "unconnected-(J2-Pad23)") (class "Default")
      (node (ref "J2") (pin "23") (pinfunction "23_23") (pintype "passive+no_connect"))
    )
    (net (code "75") (name "unconnected-(J2-Pad24)") (class "Default")
      (node (ref "J2") (pin "24") (pinfunction "24_24") (pintype "passive+no_connect"))
    )
    (net (code "76") (name "unconnected-(J2-Pad26)") (class "Default")
      (node (ref "J2") (pin "26") (pinfunction "26_26") (pintype "passive+no_connect"))
    )
    (net (code "77") (name "unconnected-(J2-Pad28)") (class "Default")
      (node (ref "J2") (pin "28") (pinfunction "28_28") (pintype "passive+no_connect"))
    )
    (net (code "78") (name "unconnected-(J2-Pad29)") (class "Default")
      (node (ref "J2") (pin "29") (pinfunction "29_29") (pintype "passive+no_connect"))
    )
    (net (code "79") (name "unconnected-(J2-Pad30)") (class "Default")
      (node (ref "J2") (pin "30") (pinfunction "30_30") (pintype "passive+no_connect"))
    )
    (net (code "80") (name "unconnected-(J2-RX-Pad4)") (class "Default")
      (node (ref "J2") (pin "4") (pinfunction "RX_4") (pintype "passive+no_connect"))
    )
    (net (code "81") (name "unconnected-(J2-TX-Pad6)") (class "Default")
      (node (ref "J2") (pin "6") (pinfunction "TX_6") (pintype "passive+no_connect"))
    )
    (net (code "82") (name "unconnected-(J3-Pad1)") (class "Default")
      (node (ref "J3") (pin "1") (pinfunction "1_1") (pintype "passive+no_connect"))
    )
    (net (code "83") (name "unconnected-(J3-Pad2)") (class "Default")
      (node (ref "J3") (pin "2") (pinfunction "2_2") (pintype "passive+no_connect"))
    )
    (net (code "84") (name "unconnected-(J3-Pad3)") (class "Default")
      (node (ref "J3") (pin "3") (pinfunction "3_3") (pintype "passive+no_connect"))
    )
    (net (code "85") (name "unconnected-(J3-Pad4)") (class "Default")
      (node (ref "J3") (pin "4") (pinfunction "4_4") (pintype "passive+no_connect"))
    )
    (net (code "86") (name "unconnected-(J3-Pad5)") (class "Default")
      (node (ref "J3") (pin "5") (pinfunction "5_5") (pintype "passive+no_connect"))
    )
    (net (code "87") (name "unconnected-(J3-Pad6)") (class "Default")
      (node (ref "J3") (pin "6") (pinfunction "6_6") (pintype "passive+no_connect"))
    )
    (net (code "88") (name "unconnected-(J3-Pad7)") (class "Default")
      (node (ref "J3") (pin "7") (pinfunction "7_7") (pintype "passive+no_connect"))
    )
    (net (code "89") (name "unconnected-(J3-Pad8)") (class "Default")
      (node (ref "J3") (pin "8") (pinfunction "8_8") (pintype "passive+no_connect"))
    )
    (net (code "90") (name "unconnected-(J3-Pad9)") (class "Default")
      (node (ref "J3") (pin "9") (pinfunction "9_9") (pintype "passive+no_connect"))
    )
    (net (code "91") (name "unconnected-(J3-Pad10)") (class "Default")
      (node (ref "J3") (pin "10") (pinfunction "10_10") (pintype "passive+no_connect"))
    )
    (net (code "92") (name "unconnected-(J3-Pad11)") (class "Default")
      (node (ref "J3") (pin "11") (pinfunction "11_11") (pintype "passive+no_connect"))
    )
    (net (code "93") (name "unconnected-(J3-Pad12)") (class "Default")
      (node (ref "J3") (pin "12") (pinfunction "12_12") (pintype "passive+no_connect"))
    )
    (net (code "94") (name "unconnected-(J3-Pad13)") (class "Default")
      (node (ref "J3") (pin "13") (pinfunction "13_13") (pintype "passive+no_connect"))
    )
    (net (code "95") (name "unconnected-(J3-Pad15)") (class "Default")
      (node (ref "J3") (pin "15") (pinfunction "15_15") (pintype "passive+no_connect"))
    )
    (net (code "96") (name "unconnected-(J3-Pad17)") (class "Default")
      (node (ref "J3") (pin "17") (pinfunction "17_17") (pintype "passive+no_connect"))
    )
    (net (code "97") (name "unconnected-(J3-Pad18)") (class "Default")
      (node (ref "J3") (pin "18") (pinfunction "18_18") (pintype "passive+no_connect"))
    )
    (net (code "98") (name "unconnected-(J3-Pad19)") (class "Default")
      (node (ref "J3") (pin "19") (pinfunction "19_19") (pintype "passive+no_connect"))
    )
    (net (code "99") (name "unconnected-(J3-Pad20)") (class "Default")
      (node (ref "J3") (pin "20") (pinfunction "20_20") (pintype "passive+no_connect"))
    )
    (net (code "100") (name "unconnected-(J3-Pad21)") (class "Default")
      (node (ref "J3") (pin "21") (pinfunction "21_21") (pintype "passive+no_connect"))
    )
    (net (code "101") (name "unconnected-(J3-Pad22)") (class "Default")
      (node (ref "J3") (pin "22") (pinfunction "22_22") (pintype "passive+no_connect"))
    )
    (net (code "102") (name "unconnected-(J3-Pad23)") (class "Default")
      (node (ref "J3") (pin "23") (pinfunction "23_23") (pintype "passive+no_connect"))
    )
    (net (code "103") (name "unconnected-(J3-Pad24)") (class "Default")
      (node (ref "J3") (pin "24") (pinfunction "24_24") (pintype "passive+no_connect"))
    )
    (net (code "104") (name "unconnected-(J3-Pad25)") (class "Default")
      (node (ref "J3") (pin "25") (pinfunction "25_25") (pintype "passive+no_connect"))
    )
    (net (code "105") (name "unconnected-(J3-Pad26)") (class "Default")
      (node (ref "J3") (pin "26") (pinfunction "26_26") (pintype "passive+no_connect"))
    )
    (net (code "106") (name "unconnected-(J3-Pad27)") (class "Default")
      (node (ref "J3") (pin "27") (pinfunction "27_27") (pintype "passive+no_connect"))
    )
    (net (code "107") (name "unconnected-(J3-Pad28)") (class "Default")
      (node (ref "J3") (pin "28") (pinfunction "28_28") (pintype "passive+no_connect"))
    )
    (net (code "108") (name "unconnected-(J3-Pad29)") (class "Default")
      (node (ref "J3") (pin "29") (pinfunction "29_29") (pintype "passive+no_connect"))
    )
    (net (code "109") (name "unconnected-(J3-Pad30)") (class "Default")
      (node (ref "J3") (pin "30") (pinfunction "30_30") (pintype "passive+no_connect"))
    )
    (net (code "110") (name "unconnected-(J3-Pad31)") (class "Default")
      (node (ref "J3") (pin "31") (pinfunction "31_31") (pintype "passive+no_connect"))
    )
    (net (code "111") (name "unconnected-(J3-Pad32)") (class "Default")
      (node (ref "J3") (pin "32") (pinfunction "32_32") (pintype "passive+no_connect"))
    )
    (net (code "112") (name "unconnected-(J3-Pad33)") (class "Default")
      (node (ref "J3") (pin "33") (pinfunction "33_33") (pintype "passive+no_connect"))
    )
    (net (code "113") (name "unconnected-(J3-Pad34)") (class "Default")
      (node (ref "J3") (pin "34") (pinfunction "34_34") (pintype "passive+no_connect"))
    )
    (net (code "114") (name "unconnected-(J3-RX-Pad16)") (class "Default")
      (node (ref "J3") (pin "16") (pinfunction "RX_16") (pintype "passive+no_connect"))
    )
    (net (code "115") (name "unconnected-(J3-TX-Pad14)") (class "Default")
      (node (ref "J3") (pin "14") (pinfunction "TX_14") (pintype "passive+no_connect"))
    )
    (net (code "116") (name "unconnected-(J4-Pad1)") (class "Default")
      (node (ref "J4") (pin "1") (pinfunction "1_1") (pintype "passive+no_connect"))
    )
    (net (code "117") (name "unconnected-(J4-Pad2)") (class "Default")
      (node (ref "J4") (pin "2") (pinfunction "2_2") (pintype "passive+no_connect"))
    )
    (net (code "118") (name "unconnected-(J4-Pad3)") (class "Default")
      (node (ref "J4") (pin "3") (pinfunction "3_3") (pintype "passive+no_connect"))
    )
    (net (code "119") (name "unconnected-(J4-Pad4)") (class "Default")
      (node (ref "J4") (pin "4") (pinfunction "4_4") (pintype "passive+no_connect"))
    )
    (net (code "120") (name "unconnected-(J4-Pad5)") (class "Default")
      (node (ref "J4") (pin "5") (pinfunction "5_5") (pintype "passive+no_connect"))
    )
    (net (code "121") (name "unconnected-(J4-Pad6)") (class "Default")
      (node (ref "J4") (pin "6") (pinfunction "6_6") (pintype "passive+no_connect"))
    )
    (net (code "122") (name "unconnected-(J4-Pad7)") (class "Default")
      (node (ref "J4") (pin "7") (pinfunction "7_7") (pintype "passive+no_connect"))
    )
    (net (code "123") (name "unconnected-(J4-Pad8)") (class "Default")
      (node (ref "J4") (pin "8") (pinfunction "8_8") (pintype "passive+no_connect"))
    )
    (net (code "124") (name "unconnected-(J4-Pad9)") (class "Default")
      (node (ref "J4") (pin "9") (pinfunction "9_9") (pintype "passive+no_connect"))
    )
    (net (code "125") (name "unconnected-(J4-Pad10)") (class "Default")
      (node (ref "J4") (pin "10") (pinfunction "10_10") (pintype "passive+no_connect"))
    )
    (net (code "126") (name "unconnected-(J4-Pad11)") (class "Default")
      (node (ref "J4") (pin "11") (pinfunction "11_11") (pintype "passive+no_connect"))
    )
    (net (code "127") (name "unconnected-(J4-Pad12)") (class "Default")
      (node (ref "J4") (pin "12") (pinfunction "12_12") (pintype "passive+no_connect"))
    )
    (net (code "128") (name "unconnected-(J4-Pad13)") (class "Default")
      (node (ref "J4") (pin "13") (pinfunction "13_13") (pintype "passive+no_connect"))
    )
    (net (code "129") (name "unconnected-(J4-Pad14)") (class "Default")
      (node (ref "J4") (pin "14") (pinfunction "14_14") (pintype "passive+no_connect"))
    )
    (net (code "130") (name "unconnected-(J4-Pad15)") (class "Default")
      (node (ref "J4") (pin "15") (pinfunction "15_15") (pintype "passive+no_connect"))
    )
    (net (code "131") (name "unconnected-(J4-Pad16)") (class "Default")
      (node (ref "J4") (pin "16") (pinfunction "16_16") (pintype "passive+no_connect"))
    )
    (net (code "132") (name "unconnected-(J4-Pad17)") (class "Default")
      (node (ref "J4") (pin "17") (pinfunction "17_17") (pintype "passive+no_connect"))
    )
    (net (code "133") (name "unconnected-(J4-Pad18)") (class "Default")
      (node (ref "J4") (pin "18") (pinfunction "18_18") (pintype "passive+no_connect"))
    )
    (net (code "134") (name "unconnected-(J4-Pad19)") (class "Default")
      (node (ref "J4") (pin "19") (pinfunction "19_19") (pintype "passive+no_connect"))
    )
    (net (code "135") (name "unconnected-(J4-Pad20)") (class "Default")
      (node (ref "J4") (pin "20") (pinfunction "20_20") (pintype "passive+no_connect"))
    )
    (net (code "136") (name "unconnected-(U2-NC-Pad11)") (class "Default")
      (node (ref "U2") (pin "11") (pinfunction "NC_11") (pintype "passive+no_connect"))
    )
  )
)
